# Mother_board_USB_HUB.net
KiCad netlist of a schematic drawn in Altium Designer
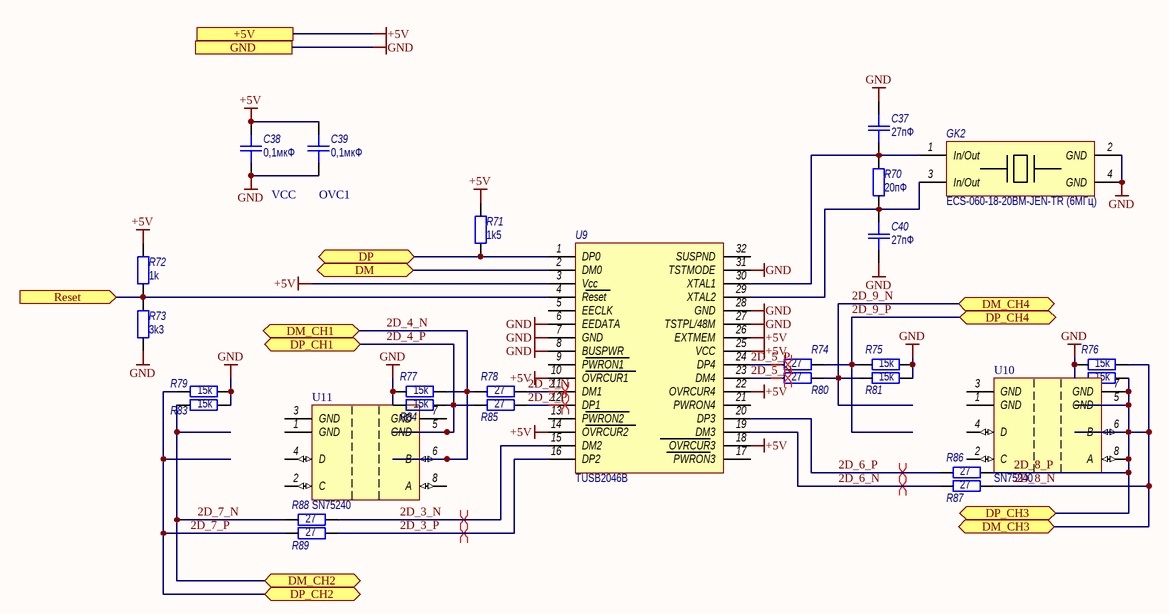
[diagram p0: Mother_board_USB_HUB.SchDoc]

(export (version "E")
  (design (tool "Eeschema 10.0.6"))
  (components
    (comp (ref "C37")
      (value "27пФ")
      (footprint "SMD_0805")
      (description "Capacitor")
      (libsource (lib "Passive") (part "Capacitor"))
    )
    (comp (ref "C38")
      (value "0,1мкФ")
      (footprint "SMD_0805")
      (description "Capacitor")
      (libsource (lib "Passive") (part "Capacitor"))
    )
    (comp (ref "C39")
      (value "0,1мкФ")
      (footprint "SMD_0805")
      (description "Capacitor")
      (libsource (lib "Passive") (part "Capacitor"))
    )
    (comp (ref "C40")
      (value "27пФ")
      (footprint "SMD_0805")
      (description "Capacitor")
      (libsource (lib "Passive") (part "Capacitor"))
    )
    (comp (ref "GK2")
      (value "~")
      (footprint "SMD_7050_Crystal_Oscillator")
      (description "Crystall")
      (fields (field (name "НАИМЕНОВАНИЕ") "ECS-060-18-20BM-JEN-TR (6МГц)"))
      (libsource (lib "Oscillator") (part "Crystal"))
    )
    (comp (ref "R70")
      (value "20пФ")
      (footprint "SMD_0805")
      (description "Resistor")
      (libsource (lib "") (part "Resistor_2"))
    )
    (comp (ref "R71")
      (value "1k5")
      (footprint "SMD_0805")
      (description "Resistor")
      (libsource (lib "") (part "Resistor_1"))
    )
    (comp (ref "R72")
      (value "1k")
      (footprint "SMD_0805")
      (description "Resistor")
      (libsource (lib "") (part "Resistor_1"))
    )
    (comp (ref "R73")
      (value "3k3")
      (footprint "SMD_0805")
      (description "Resistor")
      (libsource (lib "") (part "Resistor_1"))
    )
    (comp (ref "R74")
      (value "27")
      (footprint "SMD_0805")
      (description "Resistor")
      (libsource (lib "Passive") (part "Resistor"))
    )
    (comp (ref "R75")
      (value "15k")
      (footprint "SMD_0805")
      (description "Resistor")
      (libsource (lib "Passive") (part "Resistor"))
    )
    (comp (ref "R76")
      (value "15k")
      (footprint "SMD_0805")
      (description "Resistor")
      (libsource (lib "Passive") (part "Resistor"))
    )
    (comp (ref "R77")
      (value "15k")
      (footprint "SMD_0805")
      (description "Resistor")
      (libsource (lib "Passive") (part "Resistor"))
    )
    (comp (ref "R78")
      (value "27")
      (footprint "SMD_0805")
      (description "Resistor")
      (libsource (lib "Passive") (part "Resistor"))
    )
    (comp (ref "R79")
      (value "15k")
      (footprint "SMD_0805")
      (description "Resistor")
      (libsource (lib "Passive") (part "Resistor"))
    )
    (comp (ref "R80")
      (value "27")
      (footprint "SMD_0805")
      (description "Resistor")
      (libsource (lib "Passive") (part "Resistor"))
    )
    (comp (ref "R81")
      (value "15k")
      (footprint "SMD_0805")
      (description "Resistor")
      (libsource (lib "Passive") (part "Resistor"))
    )
    (comp (ref "R82")
      (value "15k")
      (footprint "SMD_0805")
      (description "Resistor")
      (libsource (lib "Passive") (part "Resistor"))
    )
    (comp (ref "R83")
      (value "15k")
      (footprint "SMD_0805")
      (description "Resistor")
      (libsource (lib "Passive") (part "Resistor"))
    )
    (comp (ref "R84")
      (value "15k")
      (footprint "SMD_0805")
      (description "Resistor")
      (libsource (lib "Passive") (part "Resistor"))
    )
    (comp (ref "R85")
      (value "27")
      (footprint "SMD_0805")
      (description "Resistor")
      (libsource (lib "Passive") (part "Resistor"))
    )
    (comp (ref "R86")
      (value "27")
      (footprint "SMD_0805")
      (description "Resistor")
      (libsource (lib "Passive") (part "Resistor"))
    )
    (comp (ref "R87")
      (value "27")
      (footprint "SMD_0805")
      (description "Resistor")
      (libsource (lib "Passive") (part "Resistor"))
    )
    (comp (ref "R88")
      (value "27")
      (footprint "SMD_0805")
      (description "Resistor")
      (libsource (lib "Passive") (part "Resistor"))
    )
    (comp (ref "R89")
      (value "27")
      (footprint "SMD_0805")
      (description "Resistor")
      (libsource (lib "Passive") (part "Resistor"))
    )
    (comp (ref "U9")
      (value "TUSB2046B")
      (footprint "TUSB2046B")
      (description "TUSB2046x 4-Port USB-концентратор")
      (fields (field (name "НАИМЕНОВАНИЕ") "TUSB2046B"))
      (libsource (lib "TUSB2046B") (part "TUSB2046B"))
    )
    (comp (ref "U10")
      (value "SN75240")
      (footprint "SN75240")
      (description "ESD-защита")
      (fields (field (name "НАИМЕНОВАНИЕ") "SN75240"))
      (libsource (lib "SN75240") (part "SN75240"))
    )
    (comp (ref "U11")
      (value "SN75240")
      (footprint "SN75240")
      (description "ESD-защита")
      (fields (field (name "НАИМЕНОВАНИЕ") "SN75240"))
      (libsource (lib "SN75240") (part "SN75240"))
    )
  )
  (nets
    (net (code "1") (name "+5V") (class "Default")
      (node (ref "C38") (pin "2") (pinfunction "2_2") (pintype "passive"))
      (node (ref "C39") (pin "2") (pinfunction "2_2") (pintype "passive"))
      (node (ref "R71") (pin "2") (pinfunction "2_2") (pintype "passive"))
      (node (ref "R72") (pin "2") (pinfunction "2_2") (pintype "passive"))
      (node (ref "U9") (pin "10") (pinfunction "OVRCUR1_10") (pintype "passive"))
      (node (ref "U9") (pin "14") (pinfunction "OVRCUR2_14") (pintype "passive"))
      (node (ref "U9") (pin "18") (pinfunction "OVRCUR3_18") (pintype "passive"))
      (node (ref "U9") (pin "22") (pinfunction "OVRCUR4_22") (pintype "passive"))
      (node (ref "U9") (pin "25") (pinfunction "VCC_25") (pintype "passive"))
      (node (ref "U9") (pin "26") (pinfunction "EXTMEM_26") (pintype "passive"))
      (node (ref "U9") (pin "3") (pinfunction "Vcc_3") (pintype "passive"))
    )
    (net (code "2") (name "/2D_2_N") (class "Default")
      (node (ref "R78") (pin "2") (pinfunction "2_2") (pintype "passive"))
      (node (ref "U9") (pin "11") (pinfunction "DM1_11") (pintype "passive"))
    )
    (net (code "3") (name "/2D_2_P") (class "Default")
      (node (ref "R85") (pin "2") (pinfunction "2_2") (pintype "passive"))
      (node (ref "U9") (pin "12") (pinfunction "DP1_12") (pintype "passive"))
    )
    (net (code "4") (name "/2D_3_N") (class "Default")
      (node (ref "R88") (pin "2") (pinfunction "2_2") (pintype "passive"))
      (node (ref "U9") (pin "15") (pinfunction "DM2_15") (pintype "passive"))
    )
    (net (code "5") (name "/2D_3_P") (class "Default")
      (node (ref "R89") (pin "2") (pinfunction "2_2") (pintype "passive"))
      (node (ref "U9") (pin "16") (pinfunction "DP2_16") (pintype "passive"))
    )
    (net (code "6") (name "/2D_4_N") (class "Default")
      (node (ref "R77") (pin "2") (pinfunction "2_2") (pintype "passive"))
      (node (ref "R78") (pin "1") (pinfunction "1_1") (pintype "passive"))
      (node (ref "U11") (pin "6") (pinfunction "B_6") (pintype "bidirectional"))
    )
    (net (code "7") (name "/2D_4_P") (class "Default")
      (node (ref "R84") (pin "2") (pinfunction "2_2") (pintype "passive"))
      (node (ref "R85") (pin "1") (pinfunction "1_1") (pintype "passive"))
      (node (ref "U11") (pin "5") (pinfunction "GND_5") (pintype "power_in"))
    )
    (net (code "8") (name "/2D_5_N") (class "Default")
      (node (ref "R80") (pin "1") (pinfunction "1_1") (pintype "passive"))
      (node (ref "U9") (pin "23") (pinfunction "DM4_23") (pintype "passive"))
    )
    (net (code "9") (name "/2D_5_P") (class "Default")
      (node (ref "R74") (pin "1") (pinfunction "1_1") (pintype "passive"))
      (node (ref "U9") (pin "24") (pinfunction "DP4_24") (pintype "passive"))
    )
    (net (code "10") (name "/2D_6_N") (class "Default")
      (node (ref "R87") (pin "1") (pinfunction "1_1") (pintype "passive"))
      (node (ref "U9") (pin "19") (pinfunction "DM3_19") (pintype "passive"))
    )
    (net (code "11") (name "/2D_6_P") (class "Default")
      (node (ref "R86") (pin "1") (pinfunction "1_1") (pintype "passive"))
      (node (ref "U9") (pin "20") (pinfunction "DP3_20") (pintype "passive"))
    )
    (net (code "12") (name "/2D_7_N") (class "Default")
      (node (ref "R83") (pin "1") (pinfunction "1_1") (pintype "passive"))
      (node (ref "R88") (pin "1") (pinfunction "1_1") (pintype "passive"))
    )
    (net (code "13") (name "/2D_7_P") (class "Default")
      (node (ref "R79") (pin "1") (pinfunction "1_1") (pintype "passive"))
      (node (ref "R89") (pin "1") (pinfunction "1_1") (pintype "passive"))
    )
    (net (code "14") (name "/2D_8_N") (class "Default")
      (node (ref "R76") (pin "2") (pinfunction "2_2") (pintype "passive"))
      (node (ref "R82") (pin "2") (pinfunction "2_2") (pintype "passive"))
      (node (ref "R86") (pin "2") (pinfunction "2_2") (pintype "passive"))
      (node (ref "R87") (pin "2") (pinfunction "2_2") (pintype "passive"))
      (node (ref "U10") (pin "5") (pinfunction "GND_5") (pintype "power_in"))
      (node (ref "U10") (pin "6") (pinfunction "B_6") (pintype "bidirectional"))
      (node (ref "U10") (pin "7") (pinfunction "GND_7") (pintype "power_in"))
      (node (ref "U10") (pin "8") (pinfunction "A_8") (pintype "bidirectional"))
    )
    (net (code "15") (name "/2D_9_N") (class "Default")
      (node (ref "R80") (pin "2") (pinfunction "2_2") (pintype "passive"))
      (node (ref "R81") (pin "1") (pinfunction "1_1") (pintype "passive"))
    )
    (net (code "16") (name "/2D_9_P") (class "Default")
      (node (ref "R74") (pin "2") (pinfunction "2_2") (pintype "passive"))
      (node (ref "R75") (pin "1") (pinfunction "1_1") (pintype "passive"))
    )
    (net (code "17") (name "/DM") (class "Default")
      (node (ref "U9") (pin "2") (pinfunction "DM0_2") (pintype "passive"))
    )
    (net (code "18") (name "/DP") (class "Default")
      (node (ref "R71") (pin "1") (pinfunction "1_1") (pintype "passive"))
      (node (ref "U9") (pin "1") (pinfunction "DP0_1") (pintype "passive"))
    )
    (net (code "19") (name "/Reset") (class "Default")
      (node (ref "R72") (pin "1") (pinfunction "1_1") (pintype "passive"))
      (node (ref "R73") (pin "2") (pinfunction "2_2") (pintype "passive"))
      (node (ref "U9") (pin "4") (pinfunction "Reset_4") (pintype "passive"))
    )
    (net (code "20") (name "GND") (class "Default")
      (node (ref "C37") (pin "2") (pinfunction "2_2") (pintype "passive"))
      (node (ref "C38") (pin "1") (pinfunction "1_1") (pintype "passive"))
      (node (ref "C39") (pin "1") (pinfunction "1_1") (pintype "passive"))
      (node (ref "C40") (pin "2") (pinfunction "2_2") (pintype "passive"))
      (node (ref "GK2") (pin "2") (pinfunction "GND_2") (pintype "passive"))
      (node (ref "GK2") (pin "4") (pinfunction "GND_4") (pintype "passive"))
      (node (ref "R73") (pin "1") (pinfunction "1_1") (pintype "passive"))
      (node (ref "R75") (pin "2") (pinfunction "2_2") (pintype "passive"))
      (node (ref "R76") (pin "1") (pinfunction "1_1") (pintype "passive"))
      (node (ref "R77") (pin "1") (pinfunction "1_1") (pintype "passive"))
      (node (ref "R79") (pin "2") (pinfunction "2_2") (pintype "passive"))
      (node (ref "R81") (pin "2") (pinfunction "2_2") (pintype "passive"))
      (node (ref "R82") (pin "1") (pinfunction "1_1") (pintype "passive"))
      (node (ref "R83") (pin "2") (pinfunction "2_2") (pintype "passive"))
      (node (ref "R84") (pin "1") (pinfunction "1_1") (pintype "passive"))
      (node (ref "U9") (pin "27") (pinfunction "TSTPL/48M_27") (pintype "passive"))
      (node (ref "U9") (pin "28") (pinfunction "GND_28") (pintype "passive"))
      (node (ref "U9") (pin "31") (pinfunction "TSTMODE_31") (pintype "passive"))
      (node (ref "U9") (pin "6") (pinfunction "EEDATA_6") (pintype "passive"))
      (node (ref "U9") (pin "7") (pinfunction "GND_7") (pintype "passive"))
      (node (ref "U9") (pin "8") (pinfunction "BUSPWR_8") (pintype "passive"))
    )
    (net (code "21") (name "Net-(U9-XTAL1)") (class "Default")
      (node (ref "C37") (pin "1") (pinfunction "1_1") (pintype "passive"))
      (node (ref "GK2") (pin "1") (pinfunction "In/Out_1") (pintype "passive"))
      (node (ref "R70") (pin "1") (pinfunction "1_1") (pintype "passive"))
      (node (ref "U9") (pin "30") (pinfunction "XTAL1_30") (pintype "passive"))
    )
    (net (code "22") (name "Net-(U9-XTAL2)") (class "Default")
      (node (ref "C40") (pin "1") (pinfunction "1_1") (pintype "passive"))
      (node (ref "GK2") (pin "3") (pinfunction "In/Out_3") (pintype "passive"))
      (node (ref "R70") (pin "2") (pinfunction "2_2") (pintype "passive"))
      (node (ref "U9") (pin "29") (pinfunction "XTAL2_29") (pintype "passive"))
    )
    (net (code "23") (name "unconnected-(U9-EECLK-Pad5)") (class "Default")
      (node (ref "U9") (pin "5") (pinfunction "EECLK_5") (pintype "passive"))
    )
    (net (code "24") (name "unconnected-(U9-PWRON1-Pad9)") (class "Default")
      (node (ref "U9") (pin "9") (pinfunction "PWRON1_9") (pintype "passive"))
    )
    (net (code "25") (name "unconnected-(U9-PWRON2-Pad13)") (class "Default")
      (node (ref "U9") (pin "13") (pinfunction "PWRON2_13") (pintype "passive"))
    )
    (net (code "26") (name "unconnected-(U9-PWRON3-Pad17)") (class "Default")
      (node (ref "U9") (pin "17") (pinfunction "PWRON3_17") (pintype "passive"))
    )
    (net (code "27") (name "unconnected-(U9-PWRON4-Pad21)") (class "Default")
      (node (ref "U9") (pin "21") (pinfunction "PWRON4_21") (pintype "passive"))
    )
    (net (code "28") (name "unconnected-(U9-SUSPND-Pad32)") (class "Default")
      (node (ref "U9") (pin "32") (pinfunction "SUSPND_32") (pintype "passive"))
    )
    (net (code "29") (name "unconnected-(U10-C-Pad2)") (class "Default")
      (node (ref "U10") (pin "2") (pinfunction "C_2") (pintype "bidirectional"))
    )
    (net (code "30") (name "unconnected-(U10-D-Pad4)") (class "Default")
      (node (ref "U10") (pin "4") (pinfunction "D_4") (pintype "bidirectional"))
    )
    (net (code "31") (name "unconnected-(U10-GND-Pad1)") (class "Default")
      (node (ref "U10") (pin "1") (pinfunction "GND_1") (pintype "power_in"))
    )
    (net (code "32") (name "unconnected-(U10-GND-Pad3)") (class "Default")
      (node (ref "U10") (pin "3") (pinfunction "GND_3") (pintype "power_in"))
    )
    (net (code "33") (name "unconnected-(U11-A-Pad8)") (class "Default")
      (node (ref "U11") (pin "8") (pinfunction "A_8") (pintype "bidirectional"))
    )
    (net (code "34") (name "unconnected-(U11-C-Pad2)") (class "Default")
      (node (ref "U11") (pin "2") (pinfunction "C_2") (pintype "bidirectional"))
    )
    (net (code "35") (name "unconnected-(U11-D-Pad4)") (class "Default")
      (node (ref "U11") (pin "4") (pinfunction "D_4") (pintype "bidirectional"))
    )
    (net (code "36") (name "unconnected-(U11-GND-Pad1)") (class "Default")
      (node (ref "U11") (pin "1") (pinfunction "GND_1") (pintype "power_in"))
    )
    (net (code "37") (name "unconnected-(U11-GND-Pad3)") (class "Default")
      (node (ref "U11") (pin "3") (pinfunction "GND_3") (pintype "power_in"))
    )
    (net (code "38") (name "unconnected-(U11-GND-Pad7)") (class "Default")
      (node (ref "U11") (pin "7") (pinfunction "GND_7") (pintype "power_in"))
    )
  )
)
